# 3-RF.net
KiCad netlist of a schematic drawn in Altium Designer
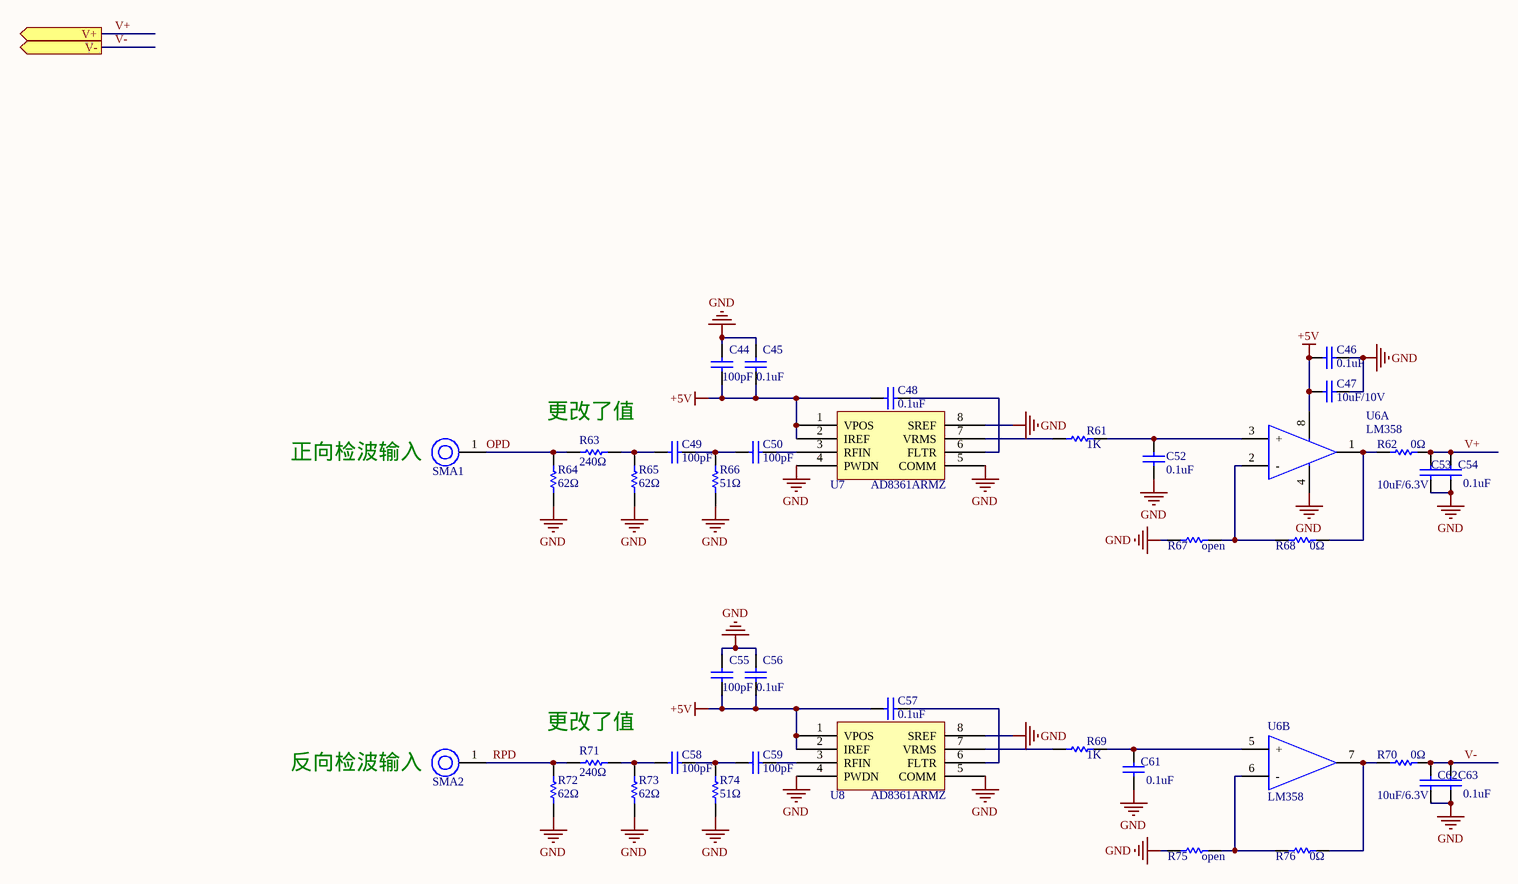
[diagram p0: 3-RF.SchDoc]

(export (version "E")
  (design (tool "Eeschema 10.0.6"))
  (components
    (comp (ref "C44")
      (value "100pF")
      (footprint "C0603")
      (description "贴片电容_100pF±10%,50V,0603")
      (libsource (lib "20贴片电容0603") (part "220pF贴片电容"))
    )
    (comp (ref "C45")
      (value "0.1uF")
      (footprint "C0603")
      (description "贴片电容_GRM188R71H104KA01D_0.1uF±10%,50V,0603")
      (libsource (lib "20贴片电容0603") (part "0.1uF贴片电容"))
    )
    (comp (ref "C46")
      (value "0.1uF")
      (footprint "C0603")
      (description "贴片电容_GRM188R71H104KA01D_0.1uF±10%,50V,0603")
      (libsource (lib "20贴片电容0603") (part "0.1uF贴片电容"))
    )
    (comp (ref "C47")
      (value "10uF/10V")
      (footprint "C0805")
      (description "贴片电容_GRM21BR61A106KE19L_10uF±10%,10V,0805")
      (libsource (lib "21贴片电容0805") (part "10uF贴片电容"))
    )
    (comp (ref "C48")
      (value "0.1uF")
      (footprint "C0603")
      (description "贴片电容_GRM188R71H104KA01D_0.1uF±10%,50V,0603")
      (libsource (lib "20贴片电容0603") (part "0.1uF贴片电容"))
    )
    (comp (ref "C49")
      (value "100pF")
      (footprint "C0805")
      (description "贴片电容_GRM2165C1H101JA01D_100pF±5%,50V,0805")
      (libsource (lib "21贴片电容0805") (part "100pF贴片电容"))
    )
    (comp (ref "C50")
      (value "100pF")
      (footprint "C0805")
      (description "贴片电容_GRM2165C1H101JA01D_100pF±5%,50V,0805")
      (libsource (lib "21贴片电容0805") (part "100pF贴片电容"))
    )
    (comp (ref "C52")
      (value "0.1uF")
      (footprint "C0603")
      (description "贴片电容_GRM188R71H104KA01D_0.1uF±10%,50V,0603")
      (libsource (lib "20贴片电容0603") (part "0.1uF贴片电容"))
    )
    (comp (ref "C53")
      (value "10uF/6.3V")
      (footprint "C0603")
      (description "贴片电容_GRM188R60J106ME47D_10uF±20%,6.3V,0603")
      (libsource (lib "20贴片电容0603") (part "10uF贴片电容"))
    )
    (comp (ref "C54")
      (value "0.1uF")
      (footprint "C0603")
      (description "贴片电容_GRM188R71H104KA01D_0.1uF±10%,50V,0603")
      (libsource (lib "20贴片电容0603") (part "0.1uF贴片电容"))
    )
    (comp (ref "C55")
      (value "100pF")
      (footprint "C0603")
      (description "贴片电容_100pF±10%,50V,0603")
      (libsource (lib "20贴片电容0603") (part "220pF贴片电容"))
    )
    (comp (ref "C56")
      (value "0.1uF")
      (footprint "C0603")
      (description "贴片电容_GRM188R71H104KA01D_0.1uF±10%,50V,0603")
      (libsource (lib "20贴片电容0603") (part "0.1uF贴片电容"))
    )
    (comp (ref "C57")
      (value "0.1uF")
      (footprint "C0603")
      (description "贴片电容_GRM188R71H104KA01D_0.1uF±10%,50V,0603")
      (libsource (lib "20贴片电容0603") (part "0.1uF贴片电容"))
    )
    (comp (ref "C58")
      (value "100pF")
      (footprint "C0805")
      (description "贴片电容_GRM2165C1H101JA01D_100pF±5%,50V,0805")
      (libsource (lib "21贴片电容0805") (part "100pF贴片电容"))
    )
    (comp (ref "C59")
      (value "100pF")
      (footprint "C0805")
      (description "贴片电容_GRM2165C1H101JA01D_100pF±5%,50V,0805")
      (libsource (lib "21贴片电容0805") (part "100pF贴片电容"))
    )
    (comp (ref "C61")
      (value "0.1uF")
      (footprint "C0603")
      (description "贴片电容_GRM188R71H104KA01D_0.1uF±10%,50V,0603")
      (libsource (lib "20贴片电容0603") (part "0.1uF贴片电容"))
    )
    (comp (ref "C62")
      (value "10uF/6.3V")
      (footprint "C0603")
      (description "贴片电容_GRM188R60J106ME47D_10uF±20%,6.3V,0603")
      (libsource (lib "20贴片电容0603") (part "10uF贴片电容"))
    )
    (comp (ref "C63")
      (value "0.1uF")
      (footprint "C0603")
      (description "贴片电容_GRM188R71H104KA01D_0.1uF±10%,50V,0603")
      (libsource (lib "20贴片电容0603") (part "0.1uF贴片电容"))
    )
    (comp (ref "R61")
      (value "1K")
      (footprint "R0603")
      (description "贴片电阻_1K±5%,0603")
      (libsource (lib "10贴片电阻0603") (part "1K贴片电阻"))
    )
    (comp (ref "R62")
      (value "0Ω")
      (footprint "R0603")
      (description "贴片电阻_0Ω±5%,0603")
      (libsource (lib "10贴片电阻0603") (part "0Ω贴片电阻"))
    )
    (comp (ref "R63")
      (value "240Ω")
      (footprint "R0805")
      (description "贴片电阻_300Ω±5%,0805")
      (libsource (lib "11贴片电阻0805") (part "300Ω贴片电阻"))
    )
    (comp (ref "R64")
      (value "62Ω")
      (footprint "R0805")
      (description "贴片电阻_62Ω±5%,0805")
      (libsource (lib "11贴片电阻0805") (part "62Ω贴片电阻"))
    )
    (comp (ref "R65")
      (value "62Ω")
      (footprint "R0805")
      (description "贴片电阻_62Ω±5%,0805")
      (libsource (lib "11贴片电阻0805") (part "62Ω贴片电阻"))
    )
    (comp (ref "R66")
      (value "51Ω")
      (footprint "R0805")
      (description "贴片电阻_51Ω±5%,0805")
      (libsource (lib "11贴片电阻0805") (part "51Ω贴片电阻"))
    )
    (comp (ref "R67") (value "open") (footprint "R0603") (libsource (lib "10贴片电阻0603") (part "0Ω贴片电阻")))
    (comp (ref "R68")
      (value "0Ω")
      (footprint "R0603")
      (description "贴片电阻_0Ω±5%,0603")
      (libsource (lib "10贴片电阻0603") (part "0Ω贴片电阻"))
    )
    (comp (ref "R69")
      (value "1K")
      (footprint "R0603")
      (description "贴片电阻_1K±5%,0603")
      (libsource (lib "10贴片电阻0603") (part "1K贴片电阻"))
    )
    (comp (ref "R70")
      (value "0Ω")
      (footprint "R0603")
      (description "贴片电阻_0Ω±5%,0603")
      (libsource (lib "10贴片电阻0603") (part "0Ω贴片电阻"))
    )
    (comp (ref "R71")
      (value "240Ω")
      (footprint "R0805")
      (description "贴片电阻_300Ω±5%,0805")
      (libsource (lib "11贴片电阻0805") (part "300Ω贴片电阻"))
    )
    (comp (ref "R72")
      (value "62Ω")
      (footprint "R0805")
      (description "贴片电阻_62Ω±5%,0805")
      (libsource (lib "11贴片电阻0805") (part "62Ω贴片电阻"))
    )
    (comp (ref "R73")
      (value "62Ω")
      (footprint "R0805")
      (description "贴片电阻_62Ω±5%,0805")
      (libsource (lib "11贴片电阻0805") (part "62Ω贴片电阻"))
    )
    (comp (ref "R74")
      (value "51Ω")
      (footprint "R0805")
      (description "贴片电阻_51Ω±5%,0805")
      (libsource (lib "11贴片电阻0805") (part "51Ω贴片电阻"))
    )
    (comp (ref "R75") (value "open") (footprint "R0603") (libsource (lib "10贴片电阻0603") (part "0Ω贴片电阻")))
    (comp (ref "R76")
      (value "0Ω")
      (footprint "R0603")
      (description "贴片电阻_0Ω±5%,0603")
      (libsource (lib "10贴片电阻0603") (part "0Ω贴片电阻"))
    )
    (comp (ref "SMA1")
      (value "SMA-50KFD-4")
      (footprint "SMA-50KFD-4")
      (description "射频同轴连接器_SMA-50KFD-4")
      (libsource (lib "90RF连接器") (part "SMA-50KFD-4"))
    )
    (comp (ref "SMA2")
      (value "SMA-50KFD-4")
      (footprint "SMA-50KFD-4")
      (description "射频同轴连接器_SMA-50KFD-4")
      (libsource (lib "90RF连接器") (part "SMA-50KFD-4"))
    )
    (comp (ref "U6")
      (value "LM358")
      (footprint "SOIC8_1R27_3R9x4R9")
      (description "运算放大器_LM358_SOIC8")
      (libsource (lib "77运算放大器") (part "LM358"))
    )
    (comp (ref "U7")
      (value "AD8361ARMZ")
      (footprint "micro_SOIC8-0R65-3x3")
      (description "检波器_AD8361ARMZ_LF to 2.5 GHz,SOIC8")
      (libsource (lib "74检波器") (part "AD8361ARMZ"))
    )
    (comp (ref "U8")
      (value "AD8361ARMZ")
      (footprint "micro_SOIC8-0R65-3x3")
      (description "检波器_AD8361ARMZ_LF to 2.5 GHz,SOIC8")
      (libsource (lib "74检波器") (part "AD8361ARMZ"))
    )
  )
  (nets
    (net (code "1") (name "+5V") (class "Default")
      (node (ref "C44") (pin "1") (pinfunction "1_1") (pintype "passive"))
      (node (ref "C45") (pin "1") (pinfunction "1_1") (pintype "passive"))
      (node (ref "C46") (pin "1") (pinfunction "1_1") (pintype "passive"))
      (node (ref "C47") (pin "1") (pinfunction "1_1") (pintype "passive"))
      (node (ref "C48") (pin "2") (pinfunction "2_2") (pintype "passive"))
      (node (ref "C55") (pin "1") (pinfunction "1_1") (pintype "passive"))
      (node (ref "C56") (pin "1") (pinfunction "1_1") (pintype "passive"))
      (node (ref "C57") (pin "2") (pinfunction "2_2") (pintype "passive"))
      (node (ref "U6") (pin "8") (pintype "passive"))
      (node (ref "U7") (pin "1") (pinfunction "VPOS_1") (pintype "passive"))
      (node (ref "U7") (pin "2") (pinfunction "IREF_2") (pintype "passive"))
      (node (ref "U8") (pin "1") (pinfunction "VPOS_1") (pintype "passive"))
      (node (ref "U8") (pin "2") (pinfunction "IREF_2") (pintype "passive"))
    )
    (net (code "2") (name "/OPD") (class "Default")
      (node (ref "R63") (pin "1") (pinfunction "1_1") (pintype "passive"))
      (node (ref "R64") (pin "2") (pinfunction "2_2") (pintype "passive"))
      (node (ref "SMA1") (pin "1") (pinfunction "Sig_1") (pintype "passive"))
    )
    (net (code "3") (name "/RPD") (class "Default")
      (node (ref "R71") (pin "1") (pinfunction "1_1") (pintype "passive"))
      (node (ref "R72") (pin "2") (pinfunction "2_2") (pintype "passive"))
      (node (ref "SMA2") (pin "1") (pinfunction "Sig_1") (pintype "passive"))
    )
    (net (code "4") (name "/V+") (class "Default")
      (node (ref "C53") (pin "2") (pinfunction "2_2") (pintype "passive"))
      (node (ref "C54") (pin "2") (pinfunction "2_2") (pintype "passive"))
      (node (ref "R62") (pin "2") (pinfunction "2_2") (pintype "passive"))
    )
    (net (code "5") (name "/V-") (class "Default")
      (node (ref "C62") (pin "2") (pinfunction "2_2") (pintype "passive"))
      (node (ref "C63") (pin "2") (pinfunction "2_2") (pintype "passive"))
      (node (ref "R70") (pin "2") (pinfunction "2_2") (pintype "passive"))
    )
    (net (code "6") (name "GND") (class "Default")
      (node (ref "C44") (pin "2") (pinfunction "2_2") (pintype "passive"))
      (node (ref "C45") (pin "2") (pinfunction "2_2") (pintype "passive"))
      (node (ref "C46") (pin "2") (pinfunction "2_2") (pintype "passive"))
      (node (ref "C47") (pin "2") (pinfunction "2_2") (pintype "passive"))
      (node (ref "C52") (pin "1") (pinfunction "1_1") (pintype "passive"))
      (node (ref "C53") (pin "1") (pinfunction "1_1") (pintype "passive"))
      (node (ref "C54") (pin "1") (pinfunction "1_1") (pintype "passive"))
      (node (ref "C55") (pin "2") (pinfunction "2_2") (pintype "passive"))
      (node (ref "C56") (pin "2") (pinfunction "2_2") (pintype "passive"))
      (node (ref "C61") (pin "1") (pinfunction "1_1") (pintype "passive"))
      (node (ref "C62") (pin "1") (pinfunction "1_1") (pintype "passive"))
      (node (ref "C63") (pin "1") (pinfunction "1_1") (pintype "passive"))
      (node (ref "R64") (pin "1") (pinfunction "1_1") (pintype "passive"))
      (node (ref "R65") (pin "1") (pinfunction "1_1") (pintype "passive"))
      (node (ref "R66") (pin "1") (pinfunction "1_1") (pintype "passive"))
      (node (ref "R67") (pin "1") (pinfunction "1_1") (pintype "passive"))
      (node (ref "R72") (pin "1") (pinfunction "1_1") (pintype "passive"))
      (node (ref "R73") (pin "1") (pinfunction "1_1") (pintype "passive"))
      (node (ref "R74") (pin "1") (pinfunction "1_1") (pintype "passive"))
      (node (ref "R75") (pin "1") (pinfunction "1_1") (pintype "passive"))
      (node (ref "U6") (pin "4") (pintype "passive"))
      (node (ref "U7") (pin "4") (pinfunction "PWDN_4") (pintype "passive"))
      (node (ref "U7") (pin "5") (pinfunction "COMM_5") (pintype "passive"))
      (node (ref "U7") (pin "8") (pinfunction "SREF_8") (pintype "passive"))
      (node (ref "U8") (pin "4") (pinfunction "PWDN_4") (pintype "passive"))
      (node (ref "U8") (pin "5") (pinfunction "COMM_5") (pintype "passive"))
      (node (ref "U8") (pin "8") (pinfunction "SREF_8") (pintype "passive"))
    )
    (net (code "7") (name "Net-(C49-Pad1)") (class "Default")
      (node (ref "C49") (pin "1") (pinfunction "1_1") (pintype "passive"))
      (node (ref "R63") (pin "2") (pinfunction "2_2") (pintype "passive"))
      (node (ref "R65") (pin "2") (pinfunction "2_2") (pintype "passive"))
    )
    (net (code "8") (name "Net-(C49-Pad2)") (class "Default")
      (node (ref "C49") (pin "2") (pinfunction "2_2") (pintype "passive"))
      (node (ref "C50") (pin "1") (pinfunction "1_1") (pintype "passive"))
      (node (ref "R66") (pin "2") (pinfunction "2_2") (pintype "passive"))
    )
    (net (code "9") (name "Net-(C58-Pad1)") (class "Default")
      (node (ref "C58") (pin "1") (pinfunction "1_1") (pintype "passive"))
      (node (ref "R71") (pin "2") (pinfunction "2_2") (pintype "passive"))
      (node (ref "R73") (pin "2") (pinfunction "2_2") (pintype "passive"))
    )
    (net (code "10") (name "Net-(C58-Pad2)") (class "Default")
      (node (ref "C58") (pin "2") (pinfunction "2_2") (pintype "passive"))
      (node (ref "C59") (pin "1") (pinfunction "1_1") (pintype "passive"))
      (node (ref "R74") (pin "2") (pinfunction "2_2") (pintype "passive"))
    )
    (net (code "11") (name "Net-(R62-Pad1)") (class "Default")
      (node (ref "R62") (pin "1") (pinfunction "1_1") (pintype "passive"))
      (node (ref "R68") (pin "2") (pinfunction "2_2") (pintype "passive"))
      (node (ref "U6") (pin "1") (pintype "passive"))
    )
    (net (code "12") (name "Net-(R70-Pad1)") (class "Default")
      (node (ref "R70") (pin "1") (pinfunction "1_1") (pintype "passive"))
      (node (ref "R76") (pin "2") (pinfunction "2_2") (pintype "passive"))
      (node (ref "U6") (pin "7") (pintype "passive"))
    )
    (net (code "13") (name "Net-(U6A-+)") (class "Default")
      (node (ref "C52") (pin "2") (pinfunction "2_2") (pintype "passive"))
      (node (ref "R61") (pin "2") (pinfunction "2_2") (pintype "passive"))
      (node (ref "U6") (pin "3") (pinfunction "+_3") (pintype "passive"))
    )
    (net (code "14") (name "Net-(U6A--)") (class "Default")
      (node (ref "R67") (pin "2") (pinfunction "2_2") (pintype "passive"))
      (node (ref "R68") (pin "1") (pinfunction "1_1") (pintype "passive"))
      (node (ref "U6") (pin "2") (pinfunction "-_2") (pintype "passive"))
    )
    (net (code "15") (name "Net-(U6B-+)") (class "Default")
      (node (ref "C61") (pin "2") (pinfunction "2_2") (pintype "passive"))
      (node (ref "R69") (pin "2") (pinfunction "2_2") (pintype "passive"))
      (node (ref "U6") (pin "5") (pinfunction "+_5") (pintype "passive"))
    )
    (net (code "16") (name "Net-(U6B--)") (class "Default")
      (node (ref "R75") (pin "2") (pinfunction "2_2") (pintype "passive"))
      (node (ref "R76") (pin "1") (pinfunction "1_1") (pintype "passive"))
      (node (ref "U6") (pin "6") (pinfunction "-_6") (pintype "passive"))
    )
    (net (code "17") (name "Net-(U7-FLTR)") (class "Default")
      (node (ref "C48") (pin "1") (pinfunction "1_1") (pintype "passive"))
      (node (ref "U7") (pin "6") (pinfunction "FLTR_6") (pintype "passive"))
    )
    (net (code "18") (name "Net-(U7-RFIN)") (class "Default")
      (node (ref "C50") (pin "2") (pinfunction "2_2") (pintype "passive"))
      (node (ref "U7") (pin "3") (pinfunction "RFIN_3") (pintype "passive"))
    )
    (net (code "19") (name "Net-(U7-VRMS)") (class "Default")
      (node (ref "R61") (pin "1") (pinfunction "1_1") (pintype "passive"))
      (node (ref "U7") (pin "7") (pinfunction "VRMS_7") (pintype "passive"))
    )
    (net (code "20") (name "Net-(U8-FLTR)") (class "Default")
      (node (ref "C57") (pin "1") (pinfunction "1_1") (pintype "passive"))
      (node (ref "U8") (pin "6") (pinfunction "FLTR_6") (pintype "passive"))
    )
    (net (code "21") (name "Net-(U8-RFIN)") (class "Default")
      (node (ref "C59") (pin "2") (pinfunction "2_2") (pintype "passive"))
      (node (ref "U8") (pin "3") (pinfunction "RFIN_3") (pintype "passive"))
    )
    (net (code "22") (name "Net-(U8-VRMS)") (class "Default")
      (node (ref "R69") (pin "1") (pinfunction "1_1") (pintype "passive"))
      (node (ref "U8") (pin "7") (pinfunction "VRMS_7") (pintype "passive"))
    )
  )
)
